# SDCard.net
KiCad netlist of a schematic drawn in Altium Designer
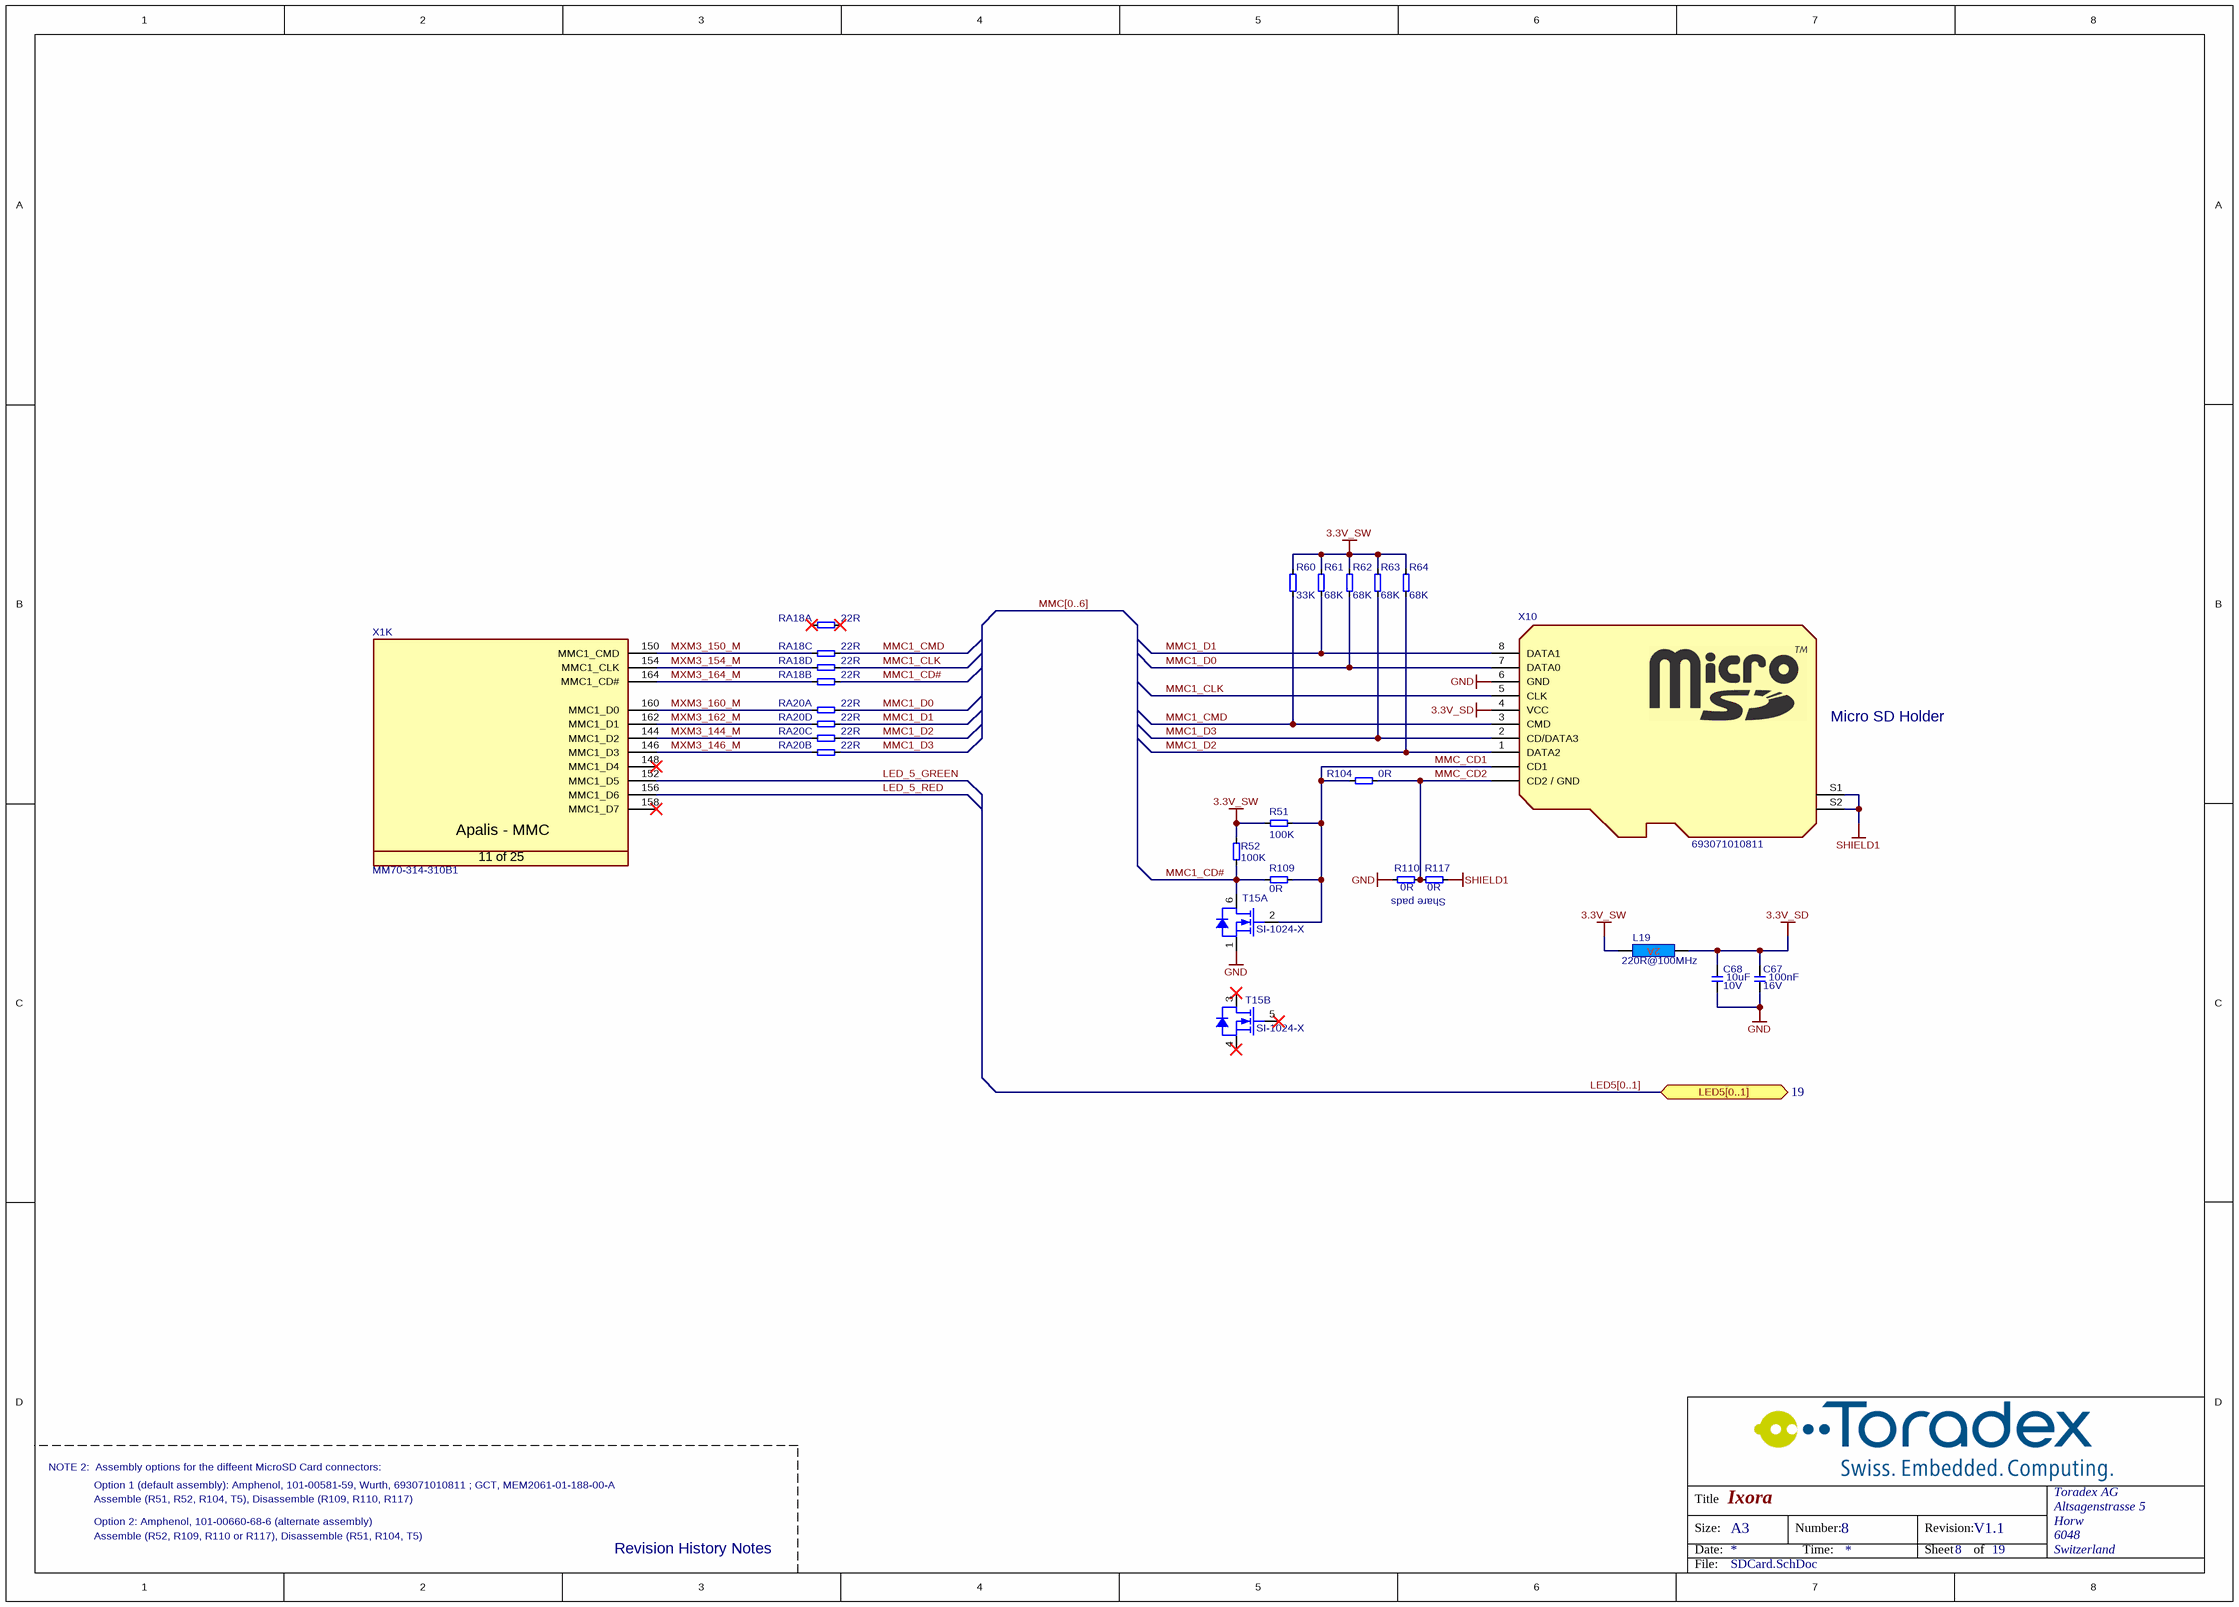
[diagram p0: SDCard.SchDoc]

(export (version "E")
  (design (tool "Eeschema 10.0.6"))
  (components
    (comp (ref "C67")
      (value "100nF")
      (footprint "CAPC1005X60N")
      (description "Capacitor Ceramic X7R 100nF 16V 10% 0402")
      (fields (field (name "TOLERANCE") "10%") (field (name "RATING") "16V"))
      (libsource (lib "Ixora") (part "C-X7R-100nF-16V-10%-0402"))
    )
    (comp (ref "C68")
      (value "10uF")
      (footprint "T_CAPC0603X33N")
      (description "Capacitor Ceramic X5R 10uF 10V 20% 0603")
      (fields (field (name "TOLERANCE") "20%") (field (name "RATING") "10V"))
      (libsource (lib "Ixora") (part "C-X5R-10uF-10V-20%-0603"))
    )
    (comp (ref "L19")
      (value "220R@100MHz")
      (footprint "INDC1608X95N")
      (description "220R@100MHz 2A EMI FILTER")
      (fields (field (name "TOLERANCE") "25%"))
      (libsource (lib "Ixora") (part "L-220R@100MHz-2A-25%-0603"))
    )
    (comp (ref "R51")
      (value "100K")
      (footprint "RESC1005X40N")
      (description "Resistor 100 Kohm 63mW 5% 0402")
      (fields (field (name "TOLERANCE") "5%"))
      (libsource (lib "Ixora") (part "R-100KR-63mW-5%-0402"))
    )
    (comp (ref "R52")
      (value "100K")
      (footprint "RESC1005X40N")
      (description "Resistor 100 Kohm 63mW 5% 0402")
      (fields (field (name "TOLERANCE") "5%"))
      (libsource (lib "Ixora") (part "R-100KR-63mW-5%-0402"))
    )
    (comp (ref "R60")
      (value "33K")
      (footprint "RESC1005X40N")
      (description "Resistor 33 Kohm 63mW 5% 0402")
      (fields (field (name "TOLERANCE") "5%"))
      (libsource (lib "Ixora") (part "R-33KR-63mW-5%-0402"))
    )
    (comp (ref "R61")
      (value "68K")
      (footprint "RESC1005X40N")
      (description "Resistor 68 Kohm 63mW 5% 0402")
      (fields (field (name "TOLERANCE") "5%"))
      (libsource (lib "Ixora") (part "R-68KR-63mW-5%-0402"))
    )
    (comp (ref "R62")
      (value "68K")
      (footprint "RESC1005X40N")
      (description "Resistor 68 Kohm 63mW 5% 0402")
      (fields (field (name "TOLERANCE") "5%"))
      (libsource (lib "Ixora") (part "R-68KR-63mW-5%-0402"))
    )
    (comp (ref "R63")
      (value "68K")
      (footprint "RESC1005X40N")
      (description "Resistor 68 Kohm 63mW 5% 0402")
      (fields (field (name "TOLERANCE") "5%"))
      (libsource (lib "Ixora") (part "R-68KR-63mW-5%-0402"))
    )
    (comp (ref "R64")
      (value "68K")
      (footprint "RESC1005X40N")
      (description "Resistor 68 Kohm 63mW 5% 0402")
      (fields (field (name "TOLERANCE") "5%"))
      (libsource (lib "Ixora") (part "R-68KR-63mW-5%-0402"))
    )
    (comp (ref "R104")
      (value "0R")
      (footprint "RESC1005X40N")
      (description "Resistor 0 ohm 63mW 1% 0402")
      (fields (field (name "TOLERANCE") "1%"))
      (libsource (lib "Ixora") (part "R-0R-63mW-1%-0402"))
    )
    (comp (ref "R109")
      (value "0R")
      (footprint "RESC1005X40N")
      (description "Resistor 0 ohm 63mW 1% 0402")
      (fields (field (name "TOLERANCE") "1%"))
      (libsource (lib "Ixora") (part "R-0R-63mW-1%-0402"))
    )
    (comp (ref "R110")
      (value "0R")
      (footprint "RESC1005X40N")
      (description "Resistor 0 ohm 63mW 1% 0402")
      (fields (field (name "TOLERANCE") "1%"))
      (libsource (lib "Ixora") (part "R-0R-63mW-1%-0402"))
    )
    (comp (ref "R117")
      (value "0R")
      (footprint "RESC1005X40N")
      (description "Resistor 0 ohm 63mW 1% 0402")
      (fields (field (name "TOLERANCE") "1%"))
      (libsource (lib "Ixora") (part "R-0R-63mW-1%-0402"))
    )
    (comp (ref "RA18")
      (value "22R")
      (footprint "T_Resistor_Array_X4")
      (description "Resistor Array 22 R 63mW 5% 1206")
      (fields (field (name "TOLERANCE") "5%"))
      (libsource (lib "Ixora") (part "RA-22R-63mW-5%-1206-div"))
    )
    (comp (ref "RA20")
      (value "22R")
      (footprint "T_Resistor_Array_X4")
      (description "Resistor Array 22 R 63mW 5% 1206")
      (fields (field (name "TOLERANCE") "5%"))
      (libsource (lib "Ixora") (part "RA-22R-63mW-5%-1206-div"))
    )
    (comp (ref "T15")
      (value "T-Vishay-SI-1024X-N")
      (footprint "SOTFL50P160X60-6N")
      (description "Dual N-Channel 20V (D-S)  MOSFET")
      (fields (field (name "MANUFACTURER PART NO.") "SI-1024-X"))
      (libsource (lib "Iris") (part "T-Vishay-SI-1024X-N"))
    )
    (comp (ref "X1")
      (value "CON-JAE-MM70-314-310B1-314-0.5mm")
      (footprint "T_JAE_MM70-314-310B1")
      (description "MXM3 Connector")
      (fields (field (name "MANUFACTURER PART NO.") "MM70-314-310B1"))
      (libsource (lib "Ixora") (part "CON-JAE-MM70-314-310B1-314-0.5mm"))
    )
    (comp (ref "X10")
      (value "MicroSD Holder")
      (footprint "T_Wurth_693071010811")
      (description "Micro SD Holder Push Push CD")
      (fields (field (name "MANUFACTURER PART NO.") "693071010811"))
      (libsource (lib "Ixora") (part "CON-Wurth-693071010811"))
    )
  )
  (nets
    (net (code "11") (name "/LED_5_GREEN") (class "Default")
      (node (ref "X1") (pin "152") (pinfunction "MMC1_D5_152") (pintype "passive"))
    )
    (net (code "12") (name "/LED_5_RED") (class "Default")
      (node (ref "X1") (pin "156") (pinfunction "MMC1_D6_156") (pintype "passive"))
    )
    (net (code "13") (name "/MMC1_CD#") (class "Default")
      (node (ref "R109") (pin "1") (pinfunction "1_1") (pintype "passive"))
      (node (ref "R52") (pin "1") (pinfunction "1_1") (pintype "passive"))
      (node (ref "RA18") (pin "6") (pinfunction "6_6") (pintype "passive"))
      (node (ref "T15") (pin "6") (pinfunction "D_6") (pintype "passive"))
    )
    (net (code "14") (name "/MMC1_CLK") (class "Default")
      (node (ref "RA18") (pin "8") (pinfunction "8_8") (pintype "passive"))
      (node (ref "X10") (pin "5") (pinfunction "CLK_5") (pintype "power_in"))
    )
    (net (code "15") (name "/MMC1_CMD") (class "Default")
      (node (ref "R60") (pin "1") (pinfunction "1_1") (pintype "passive"))
      (node (ref "RA18") (pin "7") (pinfunction "7_7") (pintype "passive"))
      (node (ref "X10") (pin "3") (pinfunction "CMD_3") (pintype "passive"))
    )
    (net (code "16") (name "/MMC1_D0") (class "Default")
      (node (ref "R62") (pin "1") (pinfunction "1_1") (pintype "passive"))
      (node (ref "RA20") (pin "5") (pinfunction "5_5") (pintype "passive"))
      (node (ref "X10") (pin "7") (pinfunction "DATA0_7") (pintype "power_in"))
    )
    (net (code "17") (name "/MMC1_D1") (class "Default")
      (node (ref "R61") (pin "1") (pinfunction "1_1") (pintype "passive"))
      (node (ref "RA20") (pin "8") (pinfunction "8_8") (pintype "passive"))
      (node (ref "X10") (pin "8") (pinfunction "DATA1_8") (pintype "power_in"))
    )
    (net (code "18") (name "/MMC1_D2") (class "Default")
      (node (ref "R64") (pin "1") (pinfunction "1_1") (pintype "passive"))
      (node (ref "RA20") (pin "7") (pinfunction "7_7") (pintype "passive"))
      (node (ref "X10") (pin "1") (pinfunction "DATA2_1") (pintype "power_in"))
    )
    (net (code "19") (name "/MMC1_D3") (class "Default")
      (node (ref "R63") (pin "1") (pinfunction "1_1") (pintype "passive"))
      (node (ref "RA20") (pin "6") (pinfunction "6_6") (pintype "passive"))
      (node (ref "X10") (pin "2") (pinfunction "CD/DATA3_2") (pintype "passive"))
    )
    (net (code "21") (name "/MMC_CD1") (class "Default")
      (node (ref "R104") (pin "2") (pinfunction "2_2") (pintype "passive"))
      (node (ref "R109") (pin "2") (pinfunction "2_2") (pintype "passive"))
      (node (ref "R51") (pin "1") (pinfunction "1_1") (pintype "passive"))
      (node (ref "T15") (pin "2") (pinfunction "G_2") (pintype "passive"))
      (node (ref "X10") (pin "CD1") (pinfunction "CD1_CD1") (pintype "power_in"))
    )
    (net (code "22") (name "/MMC_CD2") (class "Default")
      (node (ref "R104") (pin "1") (pinfunction "1_1") (pintype "passive"))
      (node (ref "R110") (pin "2") (pinfunction "2_2") (pintype "passive"))
      (node (ref "R117") (pin "1") (pinfunction "1_1") (pintype "passive"))
      (node (ref "X10") (pin "CD2") (pinfunction "CD2_/_GND_CD2") (pintype "power_in"))
    )
    (net (code "23") (name "/MXM3_144_M") (class "Default")
      (node (ref "RA20") (pin "3") (pinfunction "3_3") (pintype "passive"))
      (node (ref "X1") (pin "144") (pinfunction "MMC1_D2_144") (pintype "passive"))
    )
    (net (code "24") (name "/MXM3_146_M") (class "Default")
      (node (ref "RA20") (pin "2") (pinfunction "2_2") (pintype "passive"))
      (node (ref "X1") (pin "146") (pinfunction "MMC1_D3_146") (pintype "passive"))
    )
    (net (code "25") (name "/MXM3_150_M") (class "Default")
      (node (ref "RA18") (pin "3") (pinfunction "3_3") (pintype "passive"))
      (node (ref "X1") (pin "150") (pinfunction "MMC1_CMD_150") (pintype "passive"))
    )
    (net (code "26") (name "/MXM3_154_M") (class "Default")
      (node (ref "RA18") (pin "4") (pinfunction "4_4") (pintype "passive"))
      (node (ref "X1") (pin "154") (pinfunction "MMC1_CLK_154") (pintype "passive"))
    )
    (net (code "27") (name "/MXM3_160_M") (class "Default")
      (node (ref "RA20") (pin "1") (pinfunction "1_1") (pintype "passive"))
      (node (ref "X1") (pin "160") (pinfunction "MMC1_D0_160") (pintype "passive"))
    )
    (net (code "28") (name "/MXM3_162_M") (class "Default")
      (node (ref "RA20") (pin "4") (pinfunction "4_4") (pintype "passive"))
      (node (ref "X1") (pin "162") (pinfunction "MMC1_D1_162") (pintype "passive"))
    )
    (net (code "29") (name "/MXM3_164_M") (class "Default")
      (node (ref "RA18") (pin "2") (pinfunction "2_2") (pintype "passive"))
      (node (ref "X1") (pin "164") (pinfunction "MMC1_CD#_164") (pintype "passive"))
    )
    (net (code "30") (name "3.3V_SD") (class "Default")
      (node (ref "C67") (pin "2") (pinfunction "2_2") (pintype "passive"))
      (node (ref "C68") (pin "2") (pinfunction "2_2") (pintype "passive"))
      (node (ref "L19") (pin "1") (pinfunction "1_1") (pintype "passive"))
      (node (ref "X10") (pin "4") (pinfunction "VCC_4") (pintype "passive"))
    )
    (net (code "31") (name "3.3V_SW") (class "Default")
      (node (ref "L19") (pin "2") (pinfunction "2_2") (pintype "passive"))
      (node (ref "R51") (pin "2") (pinfunction "2_2") (pintype "passive"))
      (node (ref "R52") (pin "2") (pinfunction "2_2") (pintype "passive"))
      (node (ref "R60") (pin "2") (pinfunction "2_2") (pintype "passive"))
      (node (ref "R61") (pin "2") (pinfunction "2_2") (pintype "passive"))
      (node (ref "R62") (pin "2") (pinfunction "2_2") (pintype "passive"))
      (node (ref "R63") (pin "2") (pinfunction "2_2") (pintype "passive"))
      (node (ref "R64") (pin "2") (pinfunction "2_2") (pintype "passive"))
    )
    (net (code "32") (name "GND") (class "Default")
      (node (ref "C67") (pin "1") (pinfunction "1_1") (pintype "passive"))
      (node (ref "C68") (pin "1") (pinfunction "1_1") (pintype "passive"))
      (node (ref "R110") (pin "1") (pinfunction "1_1") (pintype "passive"))
      (node (ref "T15") (pin "1") (pinfunction "S_1") (pintype "passive"))
      (node (ref "X10") (pin "6") (pinfunction "GND_6") (pintype "power_in"))
    )
    (net (code "33") (name "SHIELD1") (class "Default")
      (node (ref "R117") (pin "2") (pinfunction "2_2") (pintype "passive"))
      (node (ref "X10") (pin "S1") (pinfunction "S_S1") (pintype "passive"))
      (node (ref "X10") (pin "S2") (pinfunction "S_S2") (pintype "passive"))
    )
    (net (code "34") (name "unconnected-(RA18-Pad1)") (class "Default")
      (node (ref "RA18") (pin "1") (pinfunction "1_1") (pintype "passive+no_connect"))
    )
    (net (code "35") (name "unconnected-(RA18-Pad5)") (class "Default")
      (node (ref "RA18") (pin "5") (pinfunction "5_5") (pintype "passive+no_connect"))
    )
    (net (code "36") (name "unconnected-(T15B-D-Pad3)") (class "Default")
      (node (ref "T15") (pin "3") (pinfunction "D_3") (pintype "passive+no_connect"))
    )
    (net (code "37") (name "unconnected-(T15B-G-Pad5)") (class "Default")
      (node (ref "T15") (pin "5") (pinfunction "G_5") (pintype "passive+no_connect"))
    )
    (net (code "38") (name "unconnected-(T15B-S-Pad4)") (class "Default")
      (node (ref "T15") (pin "4") (pinfunction "S_4") (pintype "passive+no_connect"))
    )
    (net (code "39") (name "unconnected-(X1K-MMC1_D4-Pad148)") (class "Default")
      (node (ref "X1") (pin "148") (pinfunction "MMC1_D4_148") (pintype "passive+no_connect"))
    )
    (net (code "40") (name "unconnected-(X1K-MMC1_D7-Pad158)") (class "Default")
      (node (ref "X1") (pin "158") (pinfunction "MMC1_D7_158") (pintype "passive+no_connect"))
    )
  )
)
